# Buzzer_v2_SCH.net
KiCad netlist of a schematic drawn in Altium Designer
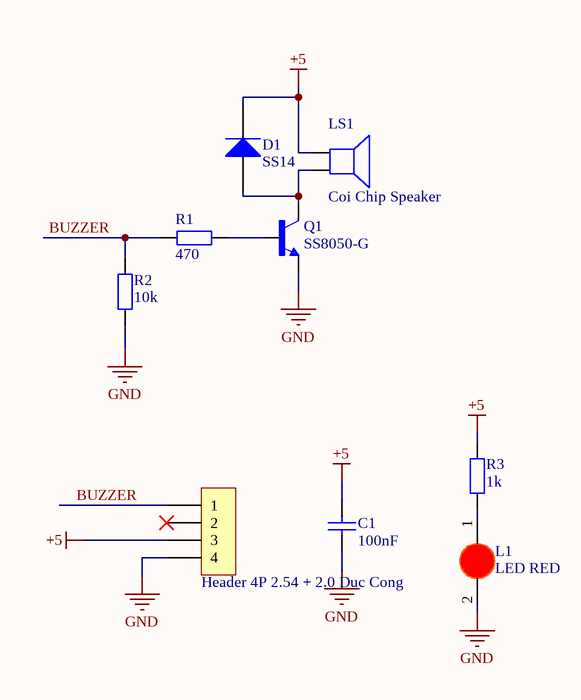
[diagram p0: Buzzer_v2_SCH.SchDoc]

(export (version "E")
  (design (tool "Eeschema 10.0.6"))
  (components
    (comp (ref "C1")
      (value "100nF")
      (footprint "tu 0603")
      (description "Dán")
      (libsource (lib "namnt_Lib") (part "Tu 0603 104 50V 10%"))
    )
    (comp (ref "D1")
      (value "SS14")
      (footprint "DIODE SMA")
      (description "Dán")
      (libsource (lib "namnt_Lib") (part "Diode SS14 ( 1N5819)"))
    )
    (comp (ref "H1")
      (value "Header 4P 2.54 + 2.0 Duc Cong")
      (footprint "Header 4P DC 2.54 + 2.0")
      (description "Cắm")
      (libsource (lib "namnt_Lib") (part "Header 4P 2.54 + 2.0 Duc Cong"))
    )
    (comp (ref "L1")
      (value "LED RED")
      (footprint "LED-0805-Red")
      (description "Dán")
      (libsource (lib "namnt_Lib") (part "LED 0805 Do"))
    )
    (comp (ref "LS1")
      (value "Coi Chip Speaker")
      (footprint "Coi Chip Speacker")
      (description "Còi chip")
      (libsource (lib "namnt_Lib") (part "Coi Chip Speaker"))
    )
    (comp (ref "Q1")
      (value "SS8050-G")
      (footprint "TRANS_SS8050-G")
      (description "Bipolar (BJT) Transistor NPN 25 V 1.5 A 100MHz 300 mW Surface Mount SOT-23-3")
      (fields (field (name "DIGI-KEY_PART_NUMBER") "641-1790-2-ND") (field (name "MP") "SS8050G"))
      (libsource (lib "namnt_Lib") (part "SS8050-G"))
    )
    (comp (ref "R1")
      (value "470")
      (footprint "tro smd 0603")
      (description "Dán")
      (libsource (lib "namnt_Lib") (part "Tro 0603 5% 100R"))
    )
    (comp (ref "R2")
      (value "10k")
      (footprint "tro smd 0603")
      (description "Dán")
      (libsource (lib "namnt_Lib") (part "Tro 0603 5% 100R"))
    )
    (comp (ref "R3")
      (value "1k")
      (footprint "tro smd 0603")
      (description "Dán")
      (libsource (lib "namnt_Lib") (part "Tro 0603 1% 1k"))
    )
  )
  (nets
    (net (code "1") (name "+5") (class "Default")
      (node (ref "C1") (pin "1") (pinfunction "1_1") (pintype "passive"))
      (node (ref "D1") (pin "2") (pinfunction "K_2") (pintype "passive"))
      (node (ref "H1") (pin "3") (pinfunction "3_3") (pintype "passive"))
      (node (ref "LS1") (pin "1") (pinfunction "1_1") (pintype "passive"))
      (node (ref "R3") (pin "2") (pinfunction "2_2") (pintype "passive"))
    )
    (net (code "2") (name "/BUZZER") (class "Default")
      (node (ref "H1") (pin "1") (pinfunction "1_1") (pintype "passive"))
      (node (ref "R1") (pin "1") (pinfunction "1_1") (pintype "passive"))
      (node (ref "R2") (pin "1") (pinfunction "1_1") (pintype "passive"))
    )
    (net (code "3") (name "GND") (class "Default")
      (node (ref "C1") (pin "2") (pinfunction "2_2") (pintype "passive"))
      (node (ref "H1") (pin "4") (pinfunction "4_4") (pintype "passive"))
      (node (ref "L1") (pin "2") (pinfunction "K_2") (pintype "passive"))
      (node (ref "Q1") (pin "2") (pinfunction "E_2") (pintype "passive"))
      (node (ref "R2") (pin "2") (pinfunction "2_2") (pintype "passive"))
    )
    (net (code "4") (name "Net-(D1-A)") (class "Default")
      (node (ref "D1") (pin "1") (pinfunction "A_1") (pintype "passive"))
      (node (ref "LS1") (pin "2") (pinfunction "2_2") (pintype "passive"))
      (node (ref "Q1") (pin "3") (pinfunction "C_3") (pintype "passive"))
    )
    (net (code "5") (name "Net-(L1-A)") (class "Default")
      (node (ref "L1") (pin "1") (pinfunction "A_1") (pintype "passive"))
      (node (ref "R3") (pin "1") (pinfunction "1_1") (pintype "passive"))
    )
    (net (code "6") (name "Net-(Q1-B)") (class "Default")
      (node (ref "Q1") (pin "1") (pinfunction "B_1") (pintype "passive"))
      (node (ref "R1") (pin "2") (pinfunction "2_2") (pintype "passive"))
    )
    (net (code "7") (name "unconnected-(H1-Pad2)") (class "Default")
      (node (ref "H1") (pin "2") (pinfunction "2_2") (pintype "passive+no_connect"))
    )
  )
)
